# Sheet_1.net
KiCad netlist of a schematic drawn in Altium Designer
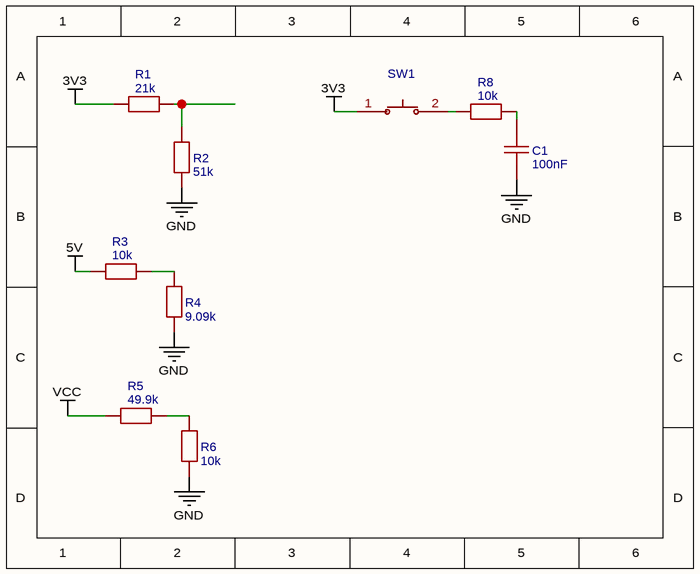
[diagram p0: Sheet_1.schdoc]

(export (version "E")
  (design (tool "Eeschema 10.0.6"))
  (components
    (comp (ref "C1")
      (value "100nF")
      (fields (field (name "CONTRIBUTOR") "LCEDA_Lib"))
      (libsource (lib "altium-import") (part "root_1_100nF_"))
    )
    (comp (ref "R1")
      (value "21k")
      (fields (field (name "CONTRIBUTOR") "LCEDA_Lib"))
      (libsource (lib "altium-import") (part "root_0_21k_"))
    )
    (comp (ref "R2")
      (value "51k")
      (fields (field (name "CONTRIBUTOR") "LCEDA_Lib"))
      (libsource (lib "altium-import") (part "root_1_51k_"))
    )
    (comp (ref "R3")
      (value "10k")
      (fields (field (name "CONTRIBUTOR") "LCEDA_Lib"))
      (libsource (lib "altium-import") (part "root_0_10k_"))
    )
    (comp (ref "R4")
      (value "9.09k")
      (fields (field (name "CONTRIBUTOR") "LCEDA_Lib"))
      (libsource (lib "altium-import") (part "root_1_9.09k_"))
    )
    (comp (ref "R5")
      (value "49.9k")
      (fields (field (name "CONTRIBUTOR") "LCEDA_Lib"))
      (libsource (lib "altium-import") (part "root_0_49.9k_"))
    )
    (comp (ref "R6")
      (value "10k")
      (fields (field (name "CONTRIBUTOR") "LCEDA_Lib"))
      (libsource (lib "altium-import") (part "root_1_10k_"))
    )
    (comp (ref "R8")
      (value "10k")
      (fields (field (name "CONTRIBUTOR") "LCEDA_Lib"))
      (libsource (lib "altium-import") (part "root_0_10k_"))
    )
    (comp (ref "SW1")
      (value "TS3625A")
      (fields (field (name "MANUFACTURER") "SHOU HAN(首韩)") (field (name "CONTRIBUTOR") "LCSC"))
      (libsource (lib "altium-import") (part "root_0_TS3625A_"))
    )
  )
  (nets
    (net (code "1") (name "3V3") (class "Default")
      (node (ref "R1") (pin "1") (pinfunction "1_1") (pintype "passive"))
      (node (ref "SW1") (pin "1") (pinfunction "1_1") (pintype "passive"))
    )
    (net (code "2") (name "5V") (class "Default")
      (node (ref "R3") (pin "1") (pinfunction "1_1") (pintype "passive"))
    )
    (net (code "3") (name "GND") (class "Default")
      (node (ref "C1") (pin "1") (pinfunction "1_1") (pintype "passive"))
      (node (ref "R2") (pin "1") (pinfunction "1_1") (pintype "passive"))
      (node (ref "R4") (pin "1") (pinfunction "1_1") (pintype "passive"))
      (node (ref "R6") (pin "1") (pinfunction "1_1") (pintype "passive"))
    )
    (net (code "4") (name "Net-(C1-Pad2)") (class "Default")
      (node (ref "C1") (pin "2") (pinfunction "2_2") (pintype "passive"))
      (node (ref "R8") (pin "2") (pinfunction "2_2") (pintype "passive"))
    )
    (net (code "5") (name "Net-(R1-Pad2)") (class "Default")
      (node (ref "R1") (pin "2") (pinfunction "2_2") (pintype "passive"))
      (node (ref "R2") (pin "2") (pinfunction "2_2") (pintype "passive"))
    )
    (net (code "6") (name "Net-(R3-Pad2)") (class "Default")
      (node (ref "R3") (pin "2") (pinfunction "2_2") (pintype "passive"))
      (node (ref "R4") (pin "2") (pinfunction "2_2") (pintype "passive"))
    )
    (net (code "7") (name "Net-(R5-Pad2)") (class "Default")
      (node (ref "R5") (pin "2") (pinfunction "2_2") (pintype "passive"))
      (node (ref "R6") (pin "2") (pinfunction "2_2") (pintype "passive"))
    )
    (net (code "8") (name "Net-(R8-Pad1)") (class "Default")
      (node (ref "R8") (pin "1") (pinfunction "1_1") (pintype "passive"))
      (node (ref "SW1") (pin "2") (pinfunction "2_2") (pintype "passive"))
    )
    (net (code "9") (name "VCC") (class "Default")
      (node (ref "R5") (pin "1") (pinfunction "1_1") (pintype "passive"))
    )
  )
)
